# tic_tac_toe_wire.net
KiCad netlist of a schematic drawn in EAGLE
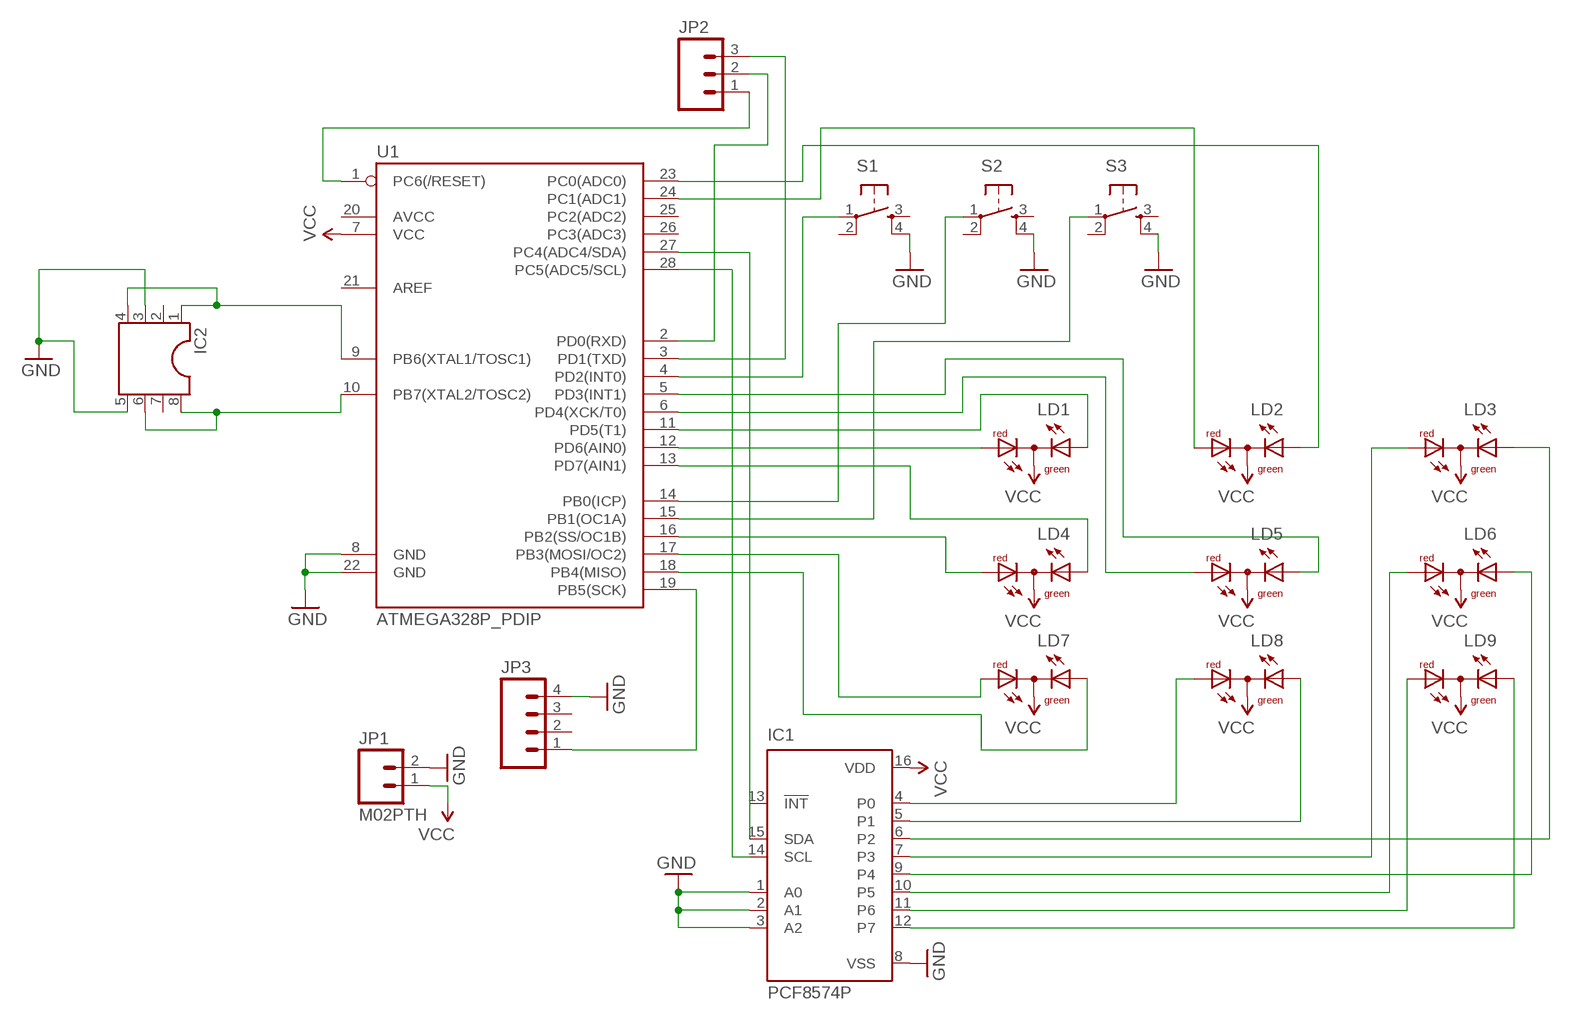
[diagram p0: schematic, sheet 1]

(export (version "E")
  (design (tool "Eeschema 10.0.6"))
  (components
    (comp (ref "IC1")
      (value "PCF8574P")
      (footprint "eagle-import:DIL16")
      (fields (field (name "MPN") "PCF8574PN"))
      (libsource (lib "eagle-import") (part "PCF8574P"))
    )
    (comp (ref "IC2")
      (value "DIL8S")
      (footprint "eagle-import:SOCKET-08")
      (libsource (lib "eagle-import") (part "DIL8S"))
    )
    (comp (ref "JP1")
      (value "M02PTH")
      (footprint "eagle-import:1X02")
      (libsource (lib "eagle-import") (part "M02PTH"))
    )
    (comp (ref "JP2")
      (value "M03PTH")
      (footprint "eagle-import:1X03")
      (libsource (lib "eagle-import") (part "M03PTH"))
    )
    (comp (ref "JP3")
      (value "M04PTH")
      (footprint "eagle-import:1X04")
      (libsource (lib "eagle-import") (part "M04PTH"))
    )
    (comp (ref "LD1")
      (value "DUOLED-RG-C")
      (footprint "eagle-import:DUOLED-C-5MM")
      (libsource (lib "eagle-import") (part "DUOLED-RG-C"))
    )
    (comp (ref "LD2")
      (value "DUOLED-RG-C")
      (footprint "eagle-import:DUOLED-C-5MM")
      (libsource (lib "eagle-import") (part "DUOLED-RG-C"))
    )
    (comp (ref "LD3")
      (value "DUOLED-RG-C")
      (footprint "eagle-import:DUOLED-C-5MM")
      (libsource (lib "eagle-import") (part "DUOLED-RG-C"))
    )
    (comp (ref "LD4")
      (value "DUOLED-RG-C")
      (footprint "eagle-import:DUOLED-C-5MM")
      (libsource (lib "eagle-import") (part "DUOLED-RG-C"))
    )
    (comp (ref "LD5")
      (value "DUOLED-RG-C")
      (footprint "eagle-import:DUOLED-C-5MM")
      (libsource (lib "eagle-import") (part "DUOLED-RG-C"))
    )
    (comp (ref "LD6")
      (value "DUOLED-RG-C")
      (footprint "eagle-import:DUOLED-C-5MM")
      (libsource (lib "eagle-import") (part "DUOLED-RG-C"))
    )
    (comp (ref "LD7")
      (value "DUOLED-RG-C")
      (footprint "eagle-import:DUOLED-C-5MM")
      (libsource (lib "eagle-import") (part "DUOLED-RG-C"))
    )
    (comp (ref "LD8")
      (value "DUOLED-RG-C")
      (footprint "eagle-import:DUOLED-C-5MM")
      (libsource (lib "eagle-import") (part "DUOLED-RG-C"))
    )
    (comp (ref "LD9")
      (value "DUOLED-RG-C")
      (footprint "eagle-import:DUOLED-C-5MM")
      (libsource (lib "eagle-import") (part "DUOLED-RG-C"))
    )
    (comp (ref "S1")
      (value "TAC_SWITCHPTH")
      (footprint "eagle-import:TACTILE-PTH")
      (libsource (lib "eagle-import") (part "TAC_SWITCHPTH"))
    )
    (comp (ref "S2")
      (value "TAC_SWITCHPTH")
      (footprint "eagle-import:TACTILE-PTH")
      (libsource (lib "eagle-import") (part "TAC_SWITCHPTH"))
    )
    (comp (ref "S3")
      (value "TAC_SWITCHPTH")
      (footprint "eagle-import:TACTILE-PTH")
      (libsource (lib "eagle-import") (part "TAC_SWITCHPTH"))
    )
    (comp (ref "U1")
      (value "ATMEGA328P_PDIP")
      (footprint "eagle-import:DIL28-3")
      (libsource (lib "eagle-import") (part "ATMEGA328P_PDIP"))
    )
  )
  (nets
    (net (code "1") (name "GND") (class "Default")
      (node (ref "IC1") (pin "1") (pinfunction "A0_1") (pintype "input"))
      (node (ref "IC1") (pin "2") (pinfunction "A1_2") (pintype "input"))
      (node (ref "IC1") (pin "3") (pinfunction "A2_3") (pintype "input"))
      (node (ref "IC1") (pin "8") (pinfunction "VSS_8") (pintype "power_in"))
      (node (ref "IC2") (pin "3") (pinfunction "3_3") (pintype "passive"))
      (node (ref "IC2") (pin "5") (pinfunction "5_5") (pintype "passive"))
      (node (ref "JP1") (pin "2") (pinfunction "2_2") (pintype "passive"))
      (node (ref "JP3") (pin "4") (pinfunction "4_4") (pintype "passive"))
      (node (ref "S1") (pin "4") (pinfunction "4_4") (pintype "passive"))
      (node (ref "S2") (pin "4") (pinfunction "4_4") (pintype "passive"))
      (node (ref "S3") (pin "4") (pinfunction "4_4") (pintype "passive"))
      (node (ref "U1") (pin "22") (pinfunction "GND_22") (pintype "bidirectional"))
      (node (ref "U1") (pin "8") (pinfunction "GND_8") (pintype "bidirectional"))
    )
    (net (code "2") (name "Net-(IC1-P0)") (class "Default")
      (node (ref "IC1") (pin "4") (pinfunction "P0_4") (pintype "bidirectional"))
      (node (ref "LD8") (pin "AR") (pinfunction "AR_AR") (pintype "passive"))
    )
    (net (code "3") (name "Net-(IC1-P1)") (class "Default")
      (node (ref "IC1") (pin "5") (pinfunction "P1_5") (pintype "bidirectional"))
      (node (ref "LD8") (pin "AX") (pinfunction "AG_AX") (pintype "passive"))
    )
    (net (code "4") (name "Net-(IC1-P2)") (class "Default")
      (node (ref "IC1") (pin "6") (pinfunction "P2_6") (pintype "bidirectional"))
      (node (ref "LD3") (pin "AX") (pinfunction "AG_AX") (pintype "passive"))
    )
    (net (code "5") (name "Net-(IC1-P3)") (class "Default")
      (node (ref "IC1") (pin "7") (pinfunction "P3_7") (pintype "bidirectional"))
      (node (ref "LD3") (pin "AR") (pinfunction "AR_AR") (pintype "passive"))
    )
    (net (code "6") (name "Net-(IC1-P4)") (class "Default")
      (node (ref "IC1") (pin "9") (pinfunction "P4_9") (pintype "bidirectional"))
      (node (ref "LD6") (pin "AX") (pinfunction "AG_AX") (pintype "passive"))
    )
    (net (code "7") (name "Net-(IC1-P5)") (class "Default")
      (node (ref "IC1") (pin "10") (pinfunction "P5_10") (pintype "bidirectional"))
      (node (ref "LD6") (pin "AR") (pinfunction "AR_AR") (pintype "passive"))
    )
    (net (code "8") (name "Net-(IC1-P6)") (class "Default")
      (node (ref "IC1") (pin "11") (pinfunction "P6_11") (pintype "bidirectional"))
      (node (ref "LD9") (pin "AR") (pinfunction "AR_AR") (pintype "passive"))
    )
    (net (code "9") (name "Net-(IC1-P7)") (class "Default")
      (node (ref "IC1") (pin "12") (pinfunction "P7_12") (pintype "bidirectional"))
      (node (ref "LD9") (pin "AX") (pinfunction "AG_AX") (pintype "passive"))
    )
    (net (code "10") (name "Net-(IC1-SCL)") (class "Default")
      (node (ref "IC1") (pin "14") (pinfunction "SCL_14") (pintype "input"))
      (node (ref "U1") (pin "28") (pinfunction "PC5(ADC5/SCL)_28") (pintype "bidirectional"))
    )
    (net (code "11") (name "Net-(IC1-SDA)") (class "Default")
      (node (ref "IC1") (pin "15") (pinfunction "SDA_15") (pintype "bidirectional"))
      (node (ref "U1") (pin "27") (pinfunction "PC4(ADC4/SDA)_27") (pintype "bidirectional"))
    )
    (net (code "12") (name "Net-(LD1-AG)") (class "Default")
      (node (ref "LD1") (pin "AX") (pinfunction "AG_AX") (pintype "passive"))
      (node (ref "U1") (pin "11") (pinfunction "PD5(T1)_11") (pintype "bidirectional"))
    )
    (net (code "13") (name "Net-(LD2-AG)") (class "Default")
      (node (ref "LD2") (pin "AX") (pinfunction "AG_AX") (pintype "passive"))
      (node (ref "U1") (pin "23") (pinfunction "PC0(ADC0)_23") (pintype "bidirectional"))
    )
    (net (code "14") (name "Net-(LD4-AG)") (class "Default")
      (node (ref "LD4") (pin "AX") (pinfunction "AG_AX") (pintype "passive"))
      (node (ref "U1") (pin "13") (pinfunction "PD7(AIN1)_13") (pintype "bidirectional"))
    )
    (net (code "15") (name "Net-(LD5-AG)") (class "Default")
      (node (ref "LD5") (pin "AX") (pinfunction "AG_AX") (pintype "passive"))
      (node (ref "U1") (pin "5") (pinfunction "PD3(INT1)_5") (pintype "bidirectional"))
    )
    (net (code "16") (name "Net-(LD7-AG)") (class "Default")
      (node (ref "LD7") (pin "AX") (pinfunction "AG_AX") (pintype "passive"))
      (node (ref "U1") (pin "18") (pinfunction "PB4(MISO)_18") (pintype "bidirectional"))
    )
    (net (code "17") (name "Net-(U1-PB0(ICP))") (class "Default")
      (node (ref "S2") (pin "1") (pinfunction "1_1") (pintype "passive"))
      (node (ref "U1") (pin "14") (pinfunction "PB0(ICP)_14") (pintype "bidirectional"))
    )
    (net (code "18") (name "Net-(U1-PB1(OC1A))") (class "Default")
      (node (ref "S3") (pin "1") (pinfunction "1_1") (pintype "passive"))
      (node (ref "U1") (pin "15") (pinfunction "PB1(OC1A)_15") (pintype "bidirectional"))
    )
    (net (code "19") (name "Net-(U1-PB2(SS{slash}OC1B))") (class "Default")
      (node (ref "LD4") (pin "AR") (pinfunction "AR_AR") (pintype "passive"))
      (node (ref "U1") (pin "16") (pinfunction "PB2(SS/OC1B)_16") (pintype "bidirectional"))
    )
    (net (code "20") (name "Net-(U1-PB3(MOSI{slash}OC2))") (class "Default")
      (node (ref "LD7") (pin "AR") (pinfunction "AR_AR") (pintype "passive"))
      (node (ref "U1") (pin "17") (pinfunction "PB3(MOSI/OC2)_17") (pintype "bidirectional"))
    )
    (net (code "21") (name "Net-(U1-PB5(SCK))") (class "Default")
      (node (ref "JP3") (pin "1") (pinfunction "1_1") (pintype "passive"))
      (node (ref "U1") (pin "19") (pinfunction "PB5(SCK)_19") (pintype "bidirectional"))
    )
    (net (code "22") (name "Net-(U1-PB6(XTAL1{slash}TOSC1))") (class "Default")
      (node (ref "IC2") (pin "1") (pinfunction "1_1") (pintype "passive"))
      (node (ref "IC2") (pin "4") (pinfunction "4_4") (pintype "passive"))
      (node (ref "U1") (pin "9") (pinfunction "PB6(XTAL1/TOSC1)_9") (pintype "bidirectional"))
    )
    (net (code "23") (name "Net-(U1-PB7(XTAL2{slash}TOSC2))") (class "Default")
      (node (ref "IC2") (pin "6") (pinfunction "6_6") (pintype "passive"))
      (node (ref "IC2") (pin "8") (pinfunction "8_8") (pintype "passive"))
      (node (ref "U1") (pin "10") (pinfunction "PB7(XTAL2/TOSC2)_10") (pintype "bidirectional"))
    )
    (net (code "24") (name "Net-(U1-PC1(ADC1))") (class "Default")
      (node (ref "LD2") (pin "AR") (pinfunction "AR_AR") (pintype "passive"))
      (node (ref "U1") (pin "24") (pinfunction "PC1(ADC1)_24") (pintype "bidirectional"))
    )
    (net (code "25") (name "Net-(U1-PC6({slash}RESET))") (class "Default")
      (node (ref "JP2") (pin "1") (pinfunction "1_1") (pintype "passive"))
      (node (ref "U1") (pin "1") (pinfunction "PC6(/RESET)_1") (pintype "bidirectional"))
    )
    (net (code "26") (name "Net-(U1-PD0(RXD))") (class "Default")
      (node (ref "JP2") (pin "2") (pinfunction "2_2") (pintype "passive"))
      (node (ref "U1") (pin "2") (pinfunction "PD0(RXD)_2") (pintype "bidirectional"))
    )
    (net (code "27") (name "Net-(U1-PD1(TXD))") (class "Default")
      (node (ref "JP2") (pin "3") (pinfunction "3_3") (pintype "passive"))
      (node (ref "U1") (pin "3") (pinfunction "PD1(TXD)_3") (pintype "bidirectional"))
    )
    (net (code "28") (name "Net-(U1-PD2(INT0))") (class "Default")
      (node (ref "S1") (pin "1") (pinfunction "1_1") (pintype "passive"))
      (node (ref "U1") (pin "4") (pinfunction "PD2(INT0)_4") (pintype "bidirectional"))
    )
    (net (code "29") (name "Net-(U1-PD4(XCK{slash}T0))") (class "Default")
      (node (ref "LD5") (pin "AR") (pinfunction "AR_AR") (pintype "passive"))
      (node (ref "U1") (pin "6") (pinfunction "PD4(XCK/T0)_6") (pintype "bidirectional"))
    )
    (net (code "30") (name "Net-(U1-PD6(AIN0))") (class "Default")
      (node (ref "LD1") (pin "AR") (pinfunction "AR_AR") (pintype "passive"))
      (node (ref "U1") (pin "12") (pinfunction "PD6(AIN0)_12") (pintype "bidirectional"))
    )
    (net (code "31") (name "VCC") (class "Default")
      (node (ref "IC1") (pin "16") (pinfunction "VDD_16") (pintype "power_in"))
      (node (ref "JP1") (pin "1") (pinfunction "1_1") (pintype "passive"))
      (node (ref "LD1") (pin "C") (pinfunction "C_C") (pintype "passive"))
      (node (ref "LD2") (pin "C") (pinfunction "C_C") (pintype "passive"))
      (node (ref "LD3") (pin "C") (pinfunction "C_C") (pintype "passive"))
      (node (ref "LD4") (pin "C") (pinfunction "C_C") (pintype "passive"))
      (node (ref "LD5") (pin "C") (pinfunction "C_C") (pintype "passive"))
      (node (ref "LD6") (pin "C") (pinfunction "C_C") (pintype "passive"))
      (node (ref "LD7") (pin "C") (pinfunction "C_C") (pintype "passive"))
      (node (ref "LD8") (pin "C") (pinfunction "C_C") (pintype "passive"))
      (node (ref "LD9") (pin "C") (pinfunction "C_C") (pintype "passive"))
      (node (ref "U1") (pin "7") (pinfunction "VCC_7") (pintype "bidirectional"))
    )
    (net (code "32") (name "unconnected-(IC1-~{INT}-Pad13)") (class "Default")
      (node (ref "IC1") (pin "13") (pinfunction "~{INT}_13") (pintype "output"))
    )
    (net (code "33") (name "unconnected-(IC2-Pad2)") (class "Default")
      (node (ref "IC2") (pin "2") (pinfunction "2_2") (pintype "passive"))
    )
    (net (code "34") (name "unconnected-(IC2-Pad7)") (class "Default")
      (node (ref "IC2") (pin "7") (pinfunction "7_7") (pintype "passive"))
    )
    (net (code "35") (name "unconnected-(JP3-Pad2)") (class "Default")
      (node (ref "JP3") (pin "2") (pinfunction "2_2") (pintype "passive"))
    )
    (net (code "36") (name "unconnected-(JP3-Pad3)") (class "Default")
      (node (ref "JP3") (pin "3") (pinfunction "3_3") (pintype "passive"))
    )
    (net (code "37") (name "unconnected-(S1-Pad2)") (class "Default")
      (node (ref "S1") (pin "2") (pinfunction "2_2") (pintype "passive"))
    )
    (net (code "38") (name "unconnected-(S1-Pad3)") (class "Default")
      (node (ref "S1") (pin "3") (pinfunction "3_3") (pintype "passive"))
    )
    (net (code "39") (name "unconnected-(S2-Pad2)") (class "Default")
      (node (ref "S2") (pin "2") (pinfunction "2_2") (pintype "passive"))
    )
    (net (code "40") (name "unconnected-(S2-Pad3)") (class "Default")
      (node (ref "S2") (pin "3") (pinfunction "3_3") (pintype "passive"))
    )
    (net (code "41") (name "unconnected-(S3-Pad2)") (class "Default")
      (node (ref "S3") (pin "2") (pinfunction "2_2") (pintype "passive"))
    )
    (net (code "42") (name "unconnected-(S3-Pad3)") (class "Default")
      (node (ref "S3") (pin "3") (pinfunction "3_3") (pintype "passive"))
    )
    (net (code "43") (name "unconnected-(U1-AREF-Pad21)") (class "Default")
      (node (ref "U1") (pin "21") (pinfunction "AREF_21") (pintype "bidirectional"))
    )
    (net (code "44") (name "unconnected-(U1-AVCC-Pad20)") (class "Default")
      (node (ref "U1") (pin "20") (pinfunction "AVCC_20") (pintype "bidirectional"))
    )
    (net (code "45") (name "unconnected-(U1-PC2(ADC2)-Pad25)") (class "Default")
      (node (ref "U1") (pin "25") (pinfunction "PC2(ADC2)_25") (pintype "bidirectional"))
    )
    (net (code "46") (name "unconnected-(U1-PC3(ADC3)-Pad26)") (class "Default")
      (node (ref "U1") (pin "26") (pinfunction "PC3(ADC3)_26") (pintype "bidirectional"))
    )
  )
)
